# l293d.net
KiCad netlist of a schematic drawn in EAGLE
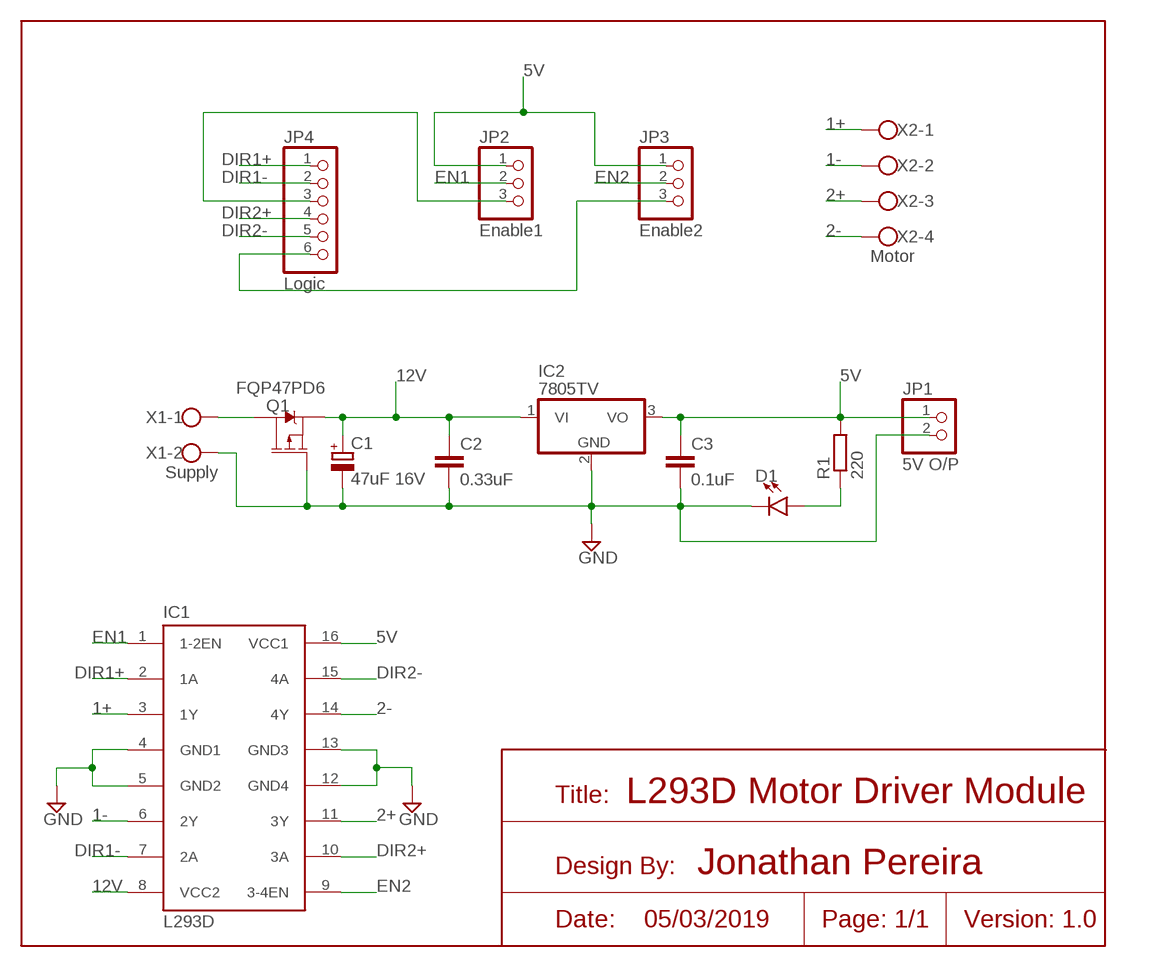
[diagram p0: schematic, sheet 1]

(export (version "E")
  (design (tool "Eeschema 10.0.6"))
  (components
    (comp (ref "C1")
      (value "47uF 16V")
      (footprint "eagle-import:E2,5-5")
      (libsource (lib "eagle-import") (part "CPOL-EUE2.5-5"))
    )
    (comp (ref "C2")
      (value "0.33uF")
      (footprint "eagle-import:C025-024X044")
      (libsource (lib "eagle-import") (part "C-EU025-024X044"))
    )
    (comp (ref "C3")
      (value "0.1uF")
      (footprint "eagle-import:C025-024X044")
      (libsource (lib "eagle-import") (part "C-EU025-024X044"))
    )
    (comp (ref "D1")
      (value "LED5MM")
      (footprint "eagle-import:LED_5MM")
      (libsource (lib "eagle-import") (part "LED5MM"))
    )
    (comp (ref "IC1")
      (value "L293D")
      (footprint "eagle-import:DIL16")
      (libsource (lib "eagle-import") (part "L293D"))
    )
    (comp (ref "IC2")
      (value "7805TV")
      (footprint "eagle-import:TO220V")
      (libsource (lib "eagle-import") (part "78TV05"))
    )
    (comp (ref "JP1")
      (value "5V O/P")
      (footprint "eagle-import:1X02")
      (libsource (lib "eagle-import") (part "PINHD-1X2"))
    )
    (comp (ref "JP2")
      (value "Enable1")
      (footprint "eagle-import:1X03")
      (libsource (lib "eagle-import") (part "PINHD-1X3"))
    )
    (comp (ref "JP3")
      (value "Enable2")
      (footprint "eagle-import:1X03")
      (libsource (lib "eagle-import") (part "PINHD-1X3"))
    )
    (comp (ref "JP4")
      (value "Logic")
      (footprint "eagle-import:1X06")
      (libsource (lib "eagle-import") (part "PINHD-1X6"))
    )
    (comp (ref "Q1")
      (value "FQP47PD6")
      (footprint "eagle-import:TO220V")
      (libsource (lib "eagle-import") (part "MOSFET_PCH-NDP6020P"))
    )
    (comp (ref "R1")
      (value "220")
      (footprint "eagle-import:0204_5")
      (libsource (lib "eagle-import") (part "R-EU_0204/5"))
    )
    (comp (ref "X1")
      (value "Supply")
      (footprint "eagle-import:W237-102")
      (fields (field (name "MPN") "237-102"))
      (libsource (lib "eagle-import") (part "W237-102"))
    )
    (comp (ref "X2")
      (value "Motor")
      (footprint "eagle-import:W237-4")
      (libsource (lib "eagle-import") (part "W237-4"))
    )
  )
  (nets
    (net (code "1") (name "/1+") (class "Default")
      (node (ref "IC1") (pin "3") (pinfunction "1Y_3") (pintype "output"))
      (node (ref "X2") (pin "1") (pinfunction "KL_1") (pintype "passive"))
    )
    (net (code "2") (name "/1-") (class "Default")
      (node (ref "IC1") (pin "6") (pinfunction "2Y_6") (pintype "output"))
      (node (ref "X2") (pin "2") (pinfunction "KL_2") (pintype "passive"))
    )
    (net (code "3") (name "/2+") (class "Default")
      (node (ref "IC1") (pin "11") (pinfunction "3Y_11") (pintype "output"))
      (node (ref "X2") (pin "3") (pinfunction "KL_3") (pintype "passive"))
    )
    (net (code "4") (name "/2-") (class "Default")
      (node (ref "IC1") (pin "14") (pinfunction "4Y_14") (pintype "output"))
      (node (ref "X2") (pin "4") (pinfunction "KL_4") (pintype "passive"))
    )
    (net (code "5") (name "/5V") (class "Default")
      (node (ref "C3") (pin "1") (pinfunction "1_1") (pintype "passive"))
      (node (ref "IC1") (pin "16") (pinfunction "VCC1_16") (pintype "power_in"))
      (node (ref "IC2") (pin "3") (pinfunction "VO_3") (pintype "passive"))
      (node (ref "JP1") (pin "1") (pinfunction "1_1") (pintype "passive"))
      (node (ref "JP2") (pin "1") (pinfunction "1_1") (pintype "passive"))
      (node (ref "JP3") (pin "1") (pinfunction "1_1") (pintype "passive"))
      (node (ref "R1") (pin "2") (pinfunction "2_2") (pintype "passive"))
    )
    (net (code "6") (name "/12V") (class "Default")
      (node (ref "C1") (pin "+") (pinfunction "+_+") (pintype "passive"))
      (node (ref "C2") (pin "1") (pinfunction "1_1") (pintype "passive"))
      (node (ref "IC1") (pin "8") (pinfunction "VCC2_8") (pintype "power_in"))
      (node (ref "IC2") (pin "1") (pinfunction "VI_1") (pintype "input"))
      (node (ref "Q1") (pin "3") (pinfunction "S_3") (pintype "bidirectional"))
    )
    (net (code "7") (name "/DIR1+") (class "Default")
      (node (ref "IC1") (pin "2") (pinfunction "1A_2") (pintype "input"))
      (node (ref "JP4") (pin "1") (pinfunction "1_1") (pintype "passive"))
    )
    (net (code "8") (name "/DIR1-") (class "Default")
      (node (ref "IC1") (pin "7") (pinfunction "2A_7") (pintype "input"))
      (node (ref "JP4") (pin "2") (pinfunction "2_2") (pintype "passive"))
    )
    (net (code "9") (name "/DIR2+") (class "Default")
      (node (ref "IC1") (pin "10") (pinfunction "3A_10") (pintype "input"))
      (node (ref "JP4") (pin "4") (pinfunction "4_4") (pintype "passive"))
    )
    (net (code "10") (name "/DIR2-") (class "Default")
      (node (ref "IC1") (pin "15") (pinfunction "4A_15") (pintype "input"))
      (node (ref "JP4") (pin "5") (pinfunction "5_5") (pintype "passive"))
    )
    (net (code "11") (name "/EN1") (class "Default")
      (node (ref "IC1") (pin "1") (pinfunction "1-2EN_1") (pintype "input"))
      (node (ref "JP2") (pin "2") (pinfunction "2_2") (pintype "passive"))
    )
    (net (code "12") (name "/EN2") (class "Default")
      (node (ref "IC1") (pin "9") (pinfunction "3-4EN_9") (pintype "input"))
      (node (ref "JP3") (pin "2") (pinfunction "2_2") (pintype "passive"))
    )
    (net (code "13") (name "GND") (class "Default")
      (node (ref "C1") (pin "-") (pinfunction "-_-") (pintype "passive"))
      (node (ref "C2") (pin "2") (pinfunction "2_2") (pintype "passive"))
      (node (ref "C3") (pin "2") (pinfunction "2_2") (pintype "passive"))
      (node (ref "D1") (pin "K") (pinfunction "C_K") (pintype "passive"))
      (node (ref "IC1") (pin "12") (pinfunction "GND4_12") (pintype "power_in"))
      (node (ref "IC1") (pin "13") (pinfunction "GND3_13") (pintype "power_in"))
      (node (ref "IC1") (pin "4") (pinfunction "GND1_4") (pintype "power_in"))
      (node (ref "IC1") (pin "5") (pinfunction "GND2_5") (pintype "power_in"))
      (node (ref "IC2") (pin "2") (pinfunction "GND_2") (pintype "passive"))
      (node (ref "JP1") (pin "2") (pinfunction "2_2") (pintype "passive"))
      (node (ref "Q1") (pin "1") (pinfunction "G_1") (pintype "bidirectional"))
      (node (ref "X1") (pin "2") (pinfunction "KL_2") (pintype "passive"))
    )
    (net (code "14") (name "Net-(D1-PadA)") (class "Default")
      (node (ref "D1") (pin "A") (pinfunction "A_A") (pintype "passive"))
      (node (ref "R1") (pin "1") (pinfunction "1_1") (pintype "passive"))
    )
    (net (code "15") (name "Net-(JP2-Pad3)") (class "Default")
      (node (ref "JP2") (pin "3") (pinfunction "3_3") (pintype "passive"))
      (node (ref "JP4") (pin "3") (pinfunction "3_3") (pintype "passive"))
    )
    (net (code "16") (name "Net-(JP3-Pad3)") (class "Default")
      (node (ref "JP3") (pin "3") (pinfunction "3_3") (pintype "passive"))
      (node (ref "JP4") (pin "6") (pinfunction "6_6") (pintype "passive"))
    )
    (net (code "17") (name "Net-(Q1-D)") (class "Default")
      (node (ref "Q1") (pin "2") (pinfunction "D_2") (pintype "bidirectional"))
      (node (ref "X1") (pin "1") (pinfunction "KL_1") (pintype "passive"))
    )
  )
)
